# colorTemp_Print2.net
KiCad netlist of a schematic drawn in EAGLE
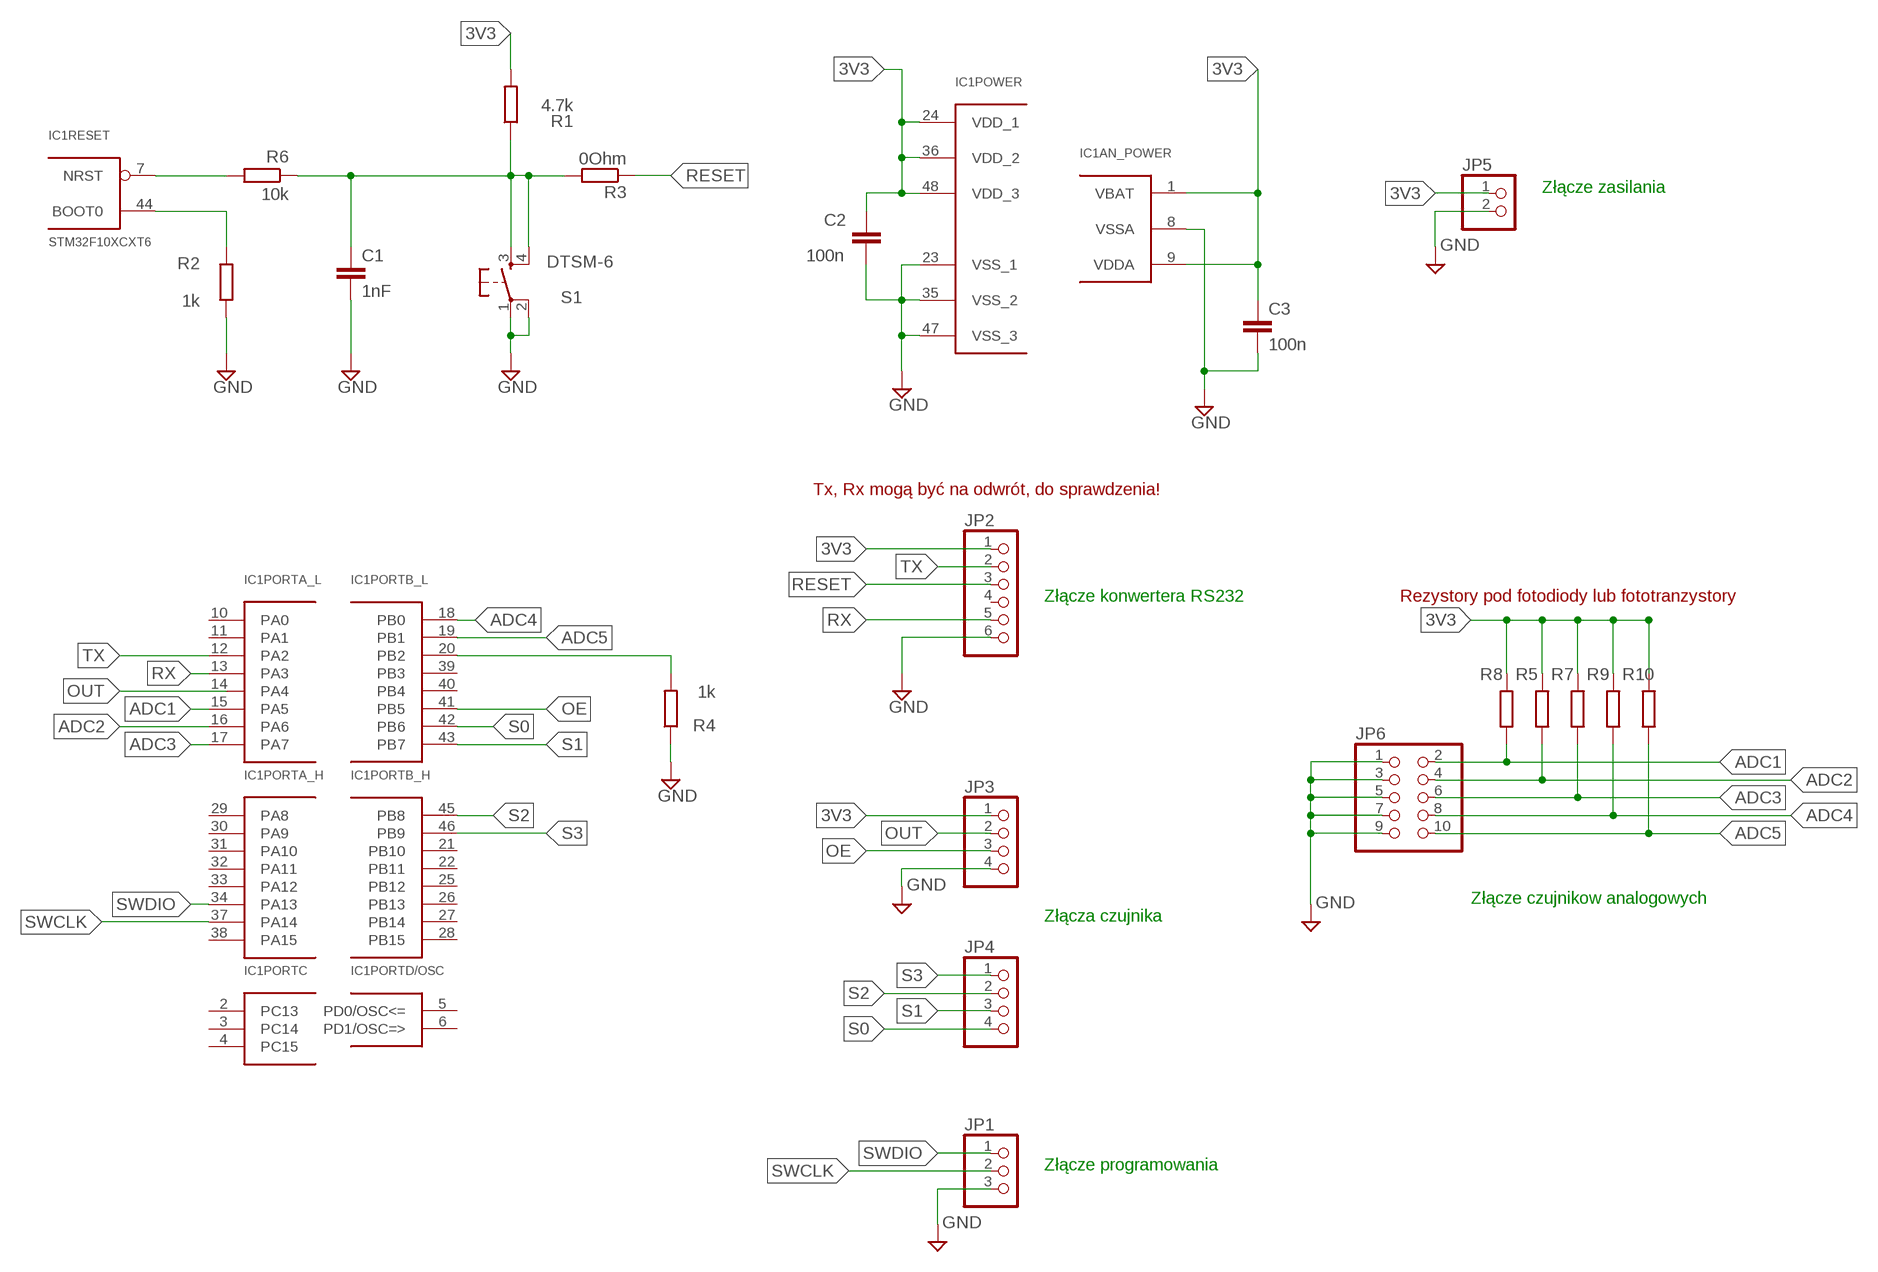
[diagram p0: schematic, sheet 1]

(export (version "E")
  (design (tool "Eeschema 10.0.6"))
  (components
    (comp (ref "C1")
      (value "1nF")
      (footprint "eagle-import:C0402")
      (libsource (lib "eagle-import") (part "C-EUC0402"))
    )
    (comp (ref "C2")
      (value "100n")
      (footprint "eagle-import:C0402")
      (libsource (lib "eagle-import") (part "C-EUC0402"))
    )
    (comp (ref "C3")
      (value "100n")
      (footprint "eagle-import:C0402")
      (libsource (lib "eagle-import") (part "C-EUC0402"))
    )
    (comp (ref "IC1")
      (value "STM32F10XCXT6")
      (footprint "eagle-import:TQFP48")
      (libsource (lib "eagle-import") (part "STM32F10XCXT6"))
    )
    (comp (ref "JP1")
      (value "PINHD-1X3")
      (footprint "eagle-import:1X03")
      (libsource (lib "eagle-import") (part "PINHD-1X3"))
    )
    (comp (ref "JP2")
      (value "PINHD-1X6/90")
      (footprint "eagle-import:1X06_90")
      (libsource (lib "eagle-import") (part "PINHD-1X6/90"))
    )
    (comp (ref "JP3")
      (value "PINHD-1X4")
      (footprint "eagle-import:1X04")
      (libsource (lib "eagle-import") (part "PINHD-1X4"))
    )
    (comp (ref "JP4")
      (value "PINHD-1X4")
      (footprint "eagle-import:1X04")
      (libsource (lib "eagle-import") (part "PINHD-1X4"))
    )
    (comp (ref "JP5")
      (value "PINHD-1X2")
      (footprint "eagle-import:1X02")
      (libsource (lib "eagle-import") (part "PINHD-1X2"))
    )
    (comp (ref "JP6")
      (value "PINHD-2X5")
      (footprint "eagle-import:2X05")
      (libsource (lib "eagle-import") (part "PINHD-2X5"))
    )
    (comp (ref "R1")
      (value "4.7k")
      (footprint "eagle-import:R0402")
      (libsource (lib "eagle-import") (part "R-EU_R0402"))
    )
    (comp (ref "R2")
      (value "1k")
      (footprint "eagle-import:R0402")
      (libsource (lib "eagle-import") (part "R-EU_R0402"))
    )
    (comp (ref "R3")
      (value "0Ohm")
      (footprint "eagle-import:R0402")
      (libsource (lib "eagle-import") (part "R-EU_R0402"))
    )
    (comp (ref "R4")
      (value "1k")
      (footprint "eagle-import:R0402")
      (libsource (lib "eagle-import") (part "R-EU_R0402"))
    )
    (comp (ref "R5")
      (value "R-EU_R0402")
      (footprint "eagle-import:R0402")
      (libsource (lib "eagle-import") (part "R-EU_R0402"))
    )
    (comp (ref "R6")
      (value "10k")
      (footprint "eagle-import:R0402")
      (libsource (lib "eagle-import") (part "R-EU_R0402"))
    )
    (comp (ref "R7")
      (value "R-EU_R0402")
      (footprint "eagle-import:R0402")
      (libsource (lib "eagle-import") (part "R-EU_R0402"))
    )
    (comp (ref "R8")
      (value "R-EU_R0402")
      (footprint "eagle-import:R0402")
      (libsource (lib "eagle-import") (part "R-EU_R0402"))
    )
    (comp (ref "R9")
      (value "R-EU_R0402")
      (footprint "eagle-import:R0402")
      (libsource (lib "eagle-import") (part "R-EU_R0402"))
    )
    (comp (ref "R10")
      (value "R-EU_R0402")
      (footprint "eagle-import:R0402")
      (libsource (lib "eagle-import") (part "R-EU_R0402"))
    )
    (comp (ref "S1")
      (value "DTSM-6")
      (footprint "eagle-import:DTSM-6")
      (libsource (lib "eagle-import") (part "DTSM-6"))
    )
  )
  (nets
    (net (code "1") (name "3V3") (class "Default")
      (node (ref "C2") (pin "1") (pinfunction "1_1") (pintype "passive"))
      (node (ref "C3") (pin "1") (pinfunction "1_1") (pintype "passive"))
      (node (ref "IC1") (pin "1") (pinfunction "VBAT_1") (pintype "power_in"))
      (node (ref "IC1") (pin "24") (pinfunction "VDD_1_24") (pintype "power_in"))
      (node (ref "IC1") (pin "36") (pinfunction "VDD_2_36") (pintype "power_in"))
      (node (ref "IC1") (pin "48") (pinfunction "VDD_3_48") (pintype "power_in"))
      (node (ref "IC1") (pin "9") (pinfunction "VDDA_9") (pintype "power_in"))
      (node (ref "JP2") (pin "1") (pinfunction "1_1") (pintype "passive"))
      (node (ref "JP3") (pin "1") (pinfunction "1_1") (pintype "passive"))
      (node (ref "JP5") (pin "1") (pinfunction "1_1") (pintype "passive"))
      (node (ref "R1") (pin "2") (pinfunction "2_2") (pintype "passive"))
      (node (ref "R10") (pin "1") (pinfunction "1_1") (pintype "passive"))
      (node (ref "R5") (pin "1") (pinfunction "1_1") (pintype "passive"))
      (node (ref "R7") (pin "1") (pinfunction "1_1") (pintype "passive"))
      (node (ref "R8") (pin "1") (pinfunction "1_1") (pintype "passive"))
      (node (ref "R9") (pin "1") (pinfunction "1_1") (pintype "passive"))
    )
    (net (code "2") (name "ADC1") (class "Default")
      (node (ref "IC1") (pin "15") (pinfunction "PA5_15") (pintype "bidirectional"))
      (node (ref "JP6") (pin "2") (pinfunction "2_2") (pintype "passive"))
      (node (ref "R8") (pin "2") (pinfunction "2_2") (pintype "passive"))
    )
    (net (code "3") (name "ADC2") (class "Default")
      (node (ref "IC1") (pin "16") (pinfunction "PA6_16") (pintype "bidirectional"))
      (node (ref "JP6") (pin "4") (pinfunction "4_4") (pintype "passive"))
      (node (ref "R5") (pin "2") (pinfunction "2_2") (pintype "passive"))
    )
    (net (code "4") (name "ADC3") (class "Default")
      (node (ref "IC1") (pin "17") (pinfunction "PA7_17") (pintype "bidirectional"))
      (node (ref "JP6") (pin "6") (pinfunction "6_6") (pintype "passive"))
      (node (ref "R7") (pin "2") (pinfunction "2_2") (pintype "passive"))
    )
    (net (code "5") (name "ADC4") (class "Default")
      (node (ref "IC1") (pin "18") (pinfunction "PB0_18") (pintype "bidirectional"))
      (node (ref "JP6") (pin "8") (pinfunction "8_8") (pintype "passive"))
      (node (ref "R9") (pin "2") (pinfunction "2_2") (pintype "passive"))
    )
    (net (code "6") (name "ADC5") (class "Default")
      (node (ref "IC1") (pin "19") (pinfunction "PB1_19") (pintype "bidirectional"))
      (node (ref "JP6") (pin "10") (pinfunction "10_10") (pintype "passive"))
      (node (ref "R10") (pin "2") (pinfunction "2_2") (pintype "passive"))
    )
    (net (code "7") (name "GND") (class "Default")
      (node (ref "C1") (pin "2") (pinfunction "2_2") (pintype "passive"))
      (node (ref "C2") (pin "2") (pinfunction "2_2") (pintype "passive"))
      (node (ref "C3") (pin "2") (pinfunction "2_2") (pintype "passive"))
      (node (ref "IC1") (pin "23") (pinfunction "VSS_1_23") (pintype "power_in"))
      (node (ref "IC1") (pin "35") (pinfunction "VSS_2_35") (pintype "power_in"))
      (node (ref "IC1") (pin "47") (pinfunction "VSS_3_47") (pintype "power_in"))
      (node (ref "IC1") (pin "8") (pinfunction "VSSA_8") (pintype "power_in"))
      (node (ref "JP1") (pin "3") (pinfunction "3_3") (pintype "passive"))
      (node (ref "JP2") (pin "6") (pinfunction "6_6") (pintype "passive"))
      (node (ref "JP3") (pin "4") (pinfunction "4_4") (pintype "passive"))
      (node (ref "JP5") (pin "2") (pinfunction "2_2") (pintype "passive"))
      (node (ref "JP6") (pin "1") (pinfunction "1_1") (pintype "passive"))
      (node (ref "JP6") (pin "3") (pinfunction "3_3") (pintype "passive"))
      (node (ref "JP6") (pin "5") (pinfunction "5_5") (pintype "passive"))
      (node (ref "JP6") (pin "7") (pinfunction "7_7") (pintype "passive"))
      (node (ref "JP6") (pin "9") (pinfunction "9_9") (pintype "passive"))
      (node (ref "R2") (pin "1") (pinfunction "1_1") (pintype "passive"))
      (node (ref "R4") (pin "1") (pinfunction "1_1") (pintype "passive"))
      (node (ref "S1") (pin "1") (pinfunction "1_1") (pintype "passive"))
      (node (ref "S1") (pin "2") (pinfunction "2_2") (pintype "passive"))
    )
    (net (code "8") (name "Net-(C1-Pad1)") (class "Default")
      (node (ref "C1") (pin "1") (pinfunction "1_1") (pintype "passive"))
      (node (ref "R1") (pin "1") (pinfunction "1_1") (pintype "passive"))
      (node (ref "R3") (pin "2") (pinfunction "2_2") (pintype "passive"))
      (node (ref "R6") (pin "1") (pinfunction "1_1") (pintype "passive"))
      (node (ref "S1") (pin "3") (pinfunction "3_3") (pintype "passive"))
      (node (ref "S1") (pin "4") (pinfunction "4_4") (pintype "passive"))
    )
    (net (code "9") (name "Net-(IC1E-PB2)") (class "Default")
      (node (ref "IC1") (pin "20") (pinfunction "PB2_20") (pintype "bidirectional"))
      (node (ref "R4") (pin "2") (pinfunction "2_2") (pintype "passive"))
    )
    (net (code "10") (name "Net-(IC1I-BOOT0)") (class "Default")
      (node (ref "IC1") (pin "44") (pinfunction "BOOT0_44") (pintype "input"))
      (node (ref "R2") (pin "2") (pinfunction "2_2") (pintype "passive"))
    )
    (net (code "11") (name "Net-(IC1I-NRST)") (class "Default")
      (node (ref "IC1") (pin "7") (pinfunction "NRST_7") (pintype "input"))
      (node (ref "R6") (pin "2") (pinfunction "2_2") (pintype "passive"))
    )
    (net (code "12") (name "OE") (class "Default")
      (node (ref "IC1") (pin "41") (pinfunction "PB5_41") (pintype "bidirectional"))
      (node (ref "JP3") (pin "3") (pinfunction "3_3") (pintype "passive"))
    )
    (net (code "13") (name "OUT") (class "Default")
      (node (ref "IC1") (pin "14") (pinfunction "PA4_14") (pintype "bidirectional"))
      (node (ref "JP3") (pin "2") (pinfunction "2_2") (pintype "passive"))
    )
    (net (code "14") (name "RESET") (class "Default")
      (node (ref "JP2") (pin "3") (pinfunction "3_3") (pintype "passive"))
      (node (ref "R3") (pin "1") (pinfunction "1_1") (pintype "passive"))
    )
    (net (code "15") (name "RX") (class "Default")
      (node (ref "IC1") (pin "13") (pinfunction "PA3_13") (pintype "bidirectional"))
      (node (ref "JP2") (pin "5") (pinfunction "5_5") (pintype "passive"))
    )
    (net (code "16") (name "S0") (class "Default")
      (node (ref "IC1") (pin "42") (pinfunction "PB6_42") (pintype "bidirectional"))
      (node (ref "JP4") (pin "4") (pinfunction "4_4") (pintype "passive"))
    )
    (net (code "17") (name "S1") (class "Default")
      (node (ref "IC1") (pin "43") (pinfunction "PB7_43") (pintype "bidirectional"))
      (node (ref "JP4") (pin "3") (pinfunction "3_3") (pintype "passive"))
    )
    (net (code "18") (name "S2") (class "Default")
      (node (ref "IC1") (pin "45") (pinfunction "PB8_45") (pintype "bidirectional"))
      (node (ref "JP4") (pin "2") (pinfunction "2_2") (pintype "passive"))
    )
    (net (code "19") (name "S3") (class "Default")
      (node (ref "IC1") (pin "46") (pinfunction "PB9_46") (pintype "bidirectional"))
      (node (ref "JP4") (pin "1") (pinfunction "1_1") (pintype "passive"))
    )
    (net (code "20") (name "SWCLK") (class "Default")
      (node (ref "IC1") (pin "37") (pinfunction "PA14_37") (pintype "bidirectional"))
      (node (ref "JP1") (pin "2") (pinfunction "2_2") (pintype "passive"))
    )
    (net (code "21") (name "SWDIO") (class "Default")
      (node (ref "IC1") (pin "34") (pinfunction "PA13_34") (pintype "bidirectional"))
      (node (ref "JP1") (pin "1") (pinfunction "1_1") (pintype "passive"))
    )
    (net (code "22") (name "TX") (class "Default")
      (node (ref "IC1") (pin "12") (pinfunction "PA2_12") (pintype "bidirectional"))
      (node (ref "JP2") (pin "2") (pinfunction "2_2") (pintype "passive"))
    )
    (net (code "23") (name "unconnected-(IC1B-PA8-Pad29)") (class "Default")
      (node (ref "IC1") (pin "29") (pinfunction "PA8_29") (pintype "bidirectional"))
    )
    (net (code "24") (name "unconnected-(IC1B-PA9-Pad30)") (class "Default")
      (node (ref "IC1") (pin "30") (pinfunction "PA9_30") (pintype "bidirectional"))
    )
    (net (code "25") (name "unconnected-(IC1B-PA10-Pad31)") (class "Default")
      (node (ref "IC1") (pin "31") (pinfunction "PA10_31") (pintype "bidirectional"))
    )
    (net (code "26") (name "unconnected-(IC1B-PA11-Pad32)") (class "Default")
      (node (ref "IC1") (pin "32") (pinfunction "PA11_32") (pintype "bidirectional"))
    )
    (net (code "27") (name "unconnected-(IC1B-PA12-Pad33)") (class "Default")
      (node (ref "IC1") (pin "33") (pinfunction "PA12_33") (pintype "bidirectional"))
    )
    (net (code "28") (name "unconnected-(IC1B-PA15-Pad38)") (class "Default")
      (node (ref "IC1") (pin "38") (pinfunction "PA15_38") (pintype "bidirectional"))
    )
    (net (code "29") (name "unconnected-(IC1C-PA0-Pad10)") (class "Default")
      (node (ref "IC1") (pin "10") (pinfunction "PA0_10") (pintype "bidirectional"))
    )
    (net (code "30") (name "unconnected-(IC1C-PA1-Pad11)") (class "Default")
      (node (ref "IC1") (pin "11") (pinfunction "PA1_11") (pintype "bidirectional"))
    )
    (net (code "31") (name "unconnected-(IC1D-PB10-Pad21)") (class "Default")
      (node (ref "IC1") (pin "21") (pinfunction "PB10_21") (pintype "bidirectional"))
    )
    (net (code "32") (name "unconnected-(IC1D-PB11-Pad22)") (class "Default")
      (node (ref "IC1") (pin "22") (pinfunction "PB11_22") (pintype "bidirectional"))
    )
    (net (code "33") (name "unconnected-(IC1D-PB12-Pad25)") (class "Default")
      (node (ref "IC1") (pin "25") (pinfunction "PB12_25") (pintype "bidirectional"))
    )
    (net (code "34") (name "unconnected-(IC1D-PB13-Pad26)") (class "Default")
      (node (ref "IC1") (pin "26") (pinfunction "PB13_26") (pintype "bidirectional"))
    )
    (net (code "35") (name "unconnected-(IC1D-PB14-Pad27)") (class "Default")
      (node (ref "IC1") (pin "27") (pinfunction "PB14_27") (pintype "bidirectional"))
    )
    (net (code "36") (name "unconnected-(IC1D-PB15-Pad28)") (class "Default")
      (node (ref "IC1") (pin "28") (pinfunction "PB15_28") (pintype "bidirectional"))
    )
    (net (code "37") (name "unconnected-(IC1E-PB3-Pad39)") (class "Default")
      (node (ref "IC1") (pin "39") (pinfunction "PB3_39") (pintype "bidirectional"))
    )
    (net (code "38") (name "unconnected-(IC1E-PB4-Pad40)") (class "Default")
      (node (ref "IC1") (pin "40") (pinfunction "PB4_40") (pintype "bidirectional"))
    )
    (net (code "39") (name "unconnected-(IC1F-PC13-Pad2)") (class "Default")
      (node (ref "IC1") (pin "2") (pinfunction "PC13_2") (pintype "bidirectional"))
    )
    (net (code "40") (name "unconnected-(IC1F-PC14-Pad3)") (class "Default")
      (node (ref "IC1") (pin "3") (pinfunction "PC14_3") (pintype "bidirectional"))
    )
    (net (code "41") (name "unconnected-(IC1F-PC15-Pad4)") (class "Default")
      (node (ref "IC1") (pin "4") (pinfunction "PC15_4") (pintype "bidirectional"))
    )
    (net (code "42") (name "unconnected-(IC1G-PD0{slash}OSC<=-Pad5)") (class "Default")
      (node (ref "IC1") (pin "5") (pinfunction "PD0/OSC<=_5") (pintype "bidirectional"))
    )
    (net (code "43") (name "unconnected-(IC1G-PD1{slash}OSC=>-Pad6)") (class "Default")
      (node (ref "IC1") (pin "6") (pinfunction "PD1/OSC=>_6") (pintype "bidirectional"))
    )
    (net (code "44") (name "unconnected-(JP2-Pad4)") (class "Default")
      (node (ref "JP2") (pin "4") (pinfunction "4_4") (pintype "passive"))
    )
  )
)
